# lymeshield_system.net
KiCad netlist of a schematic drawn in EAGLE
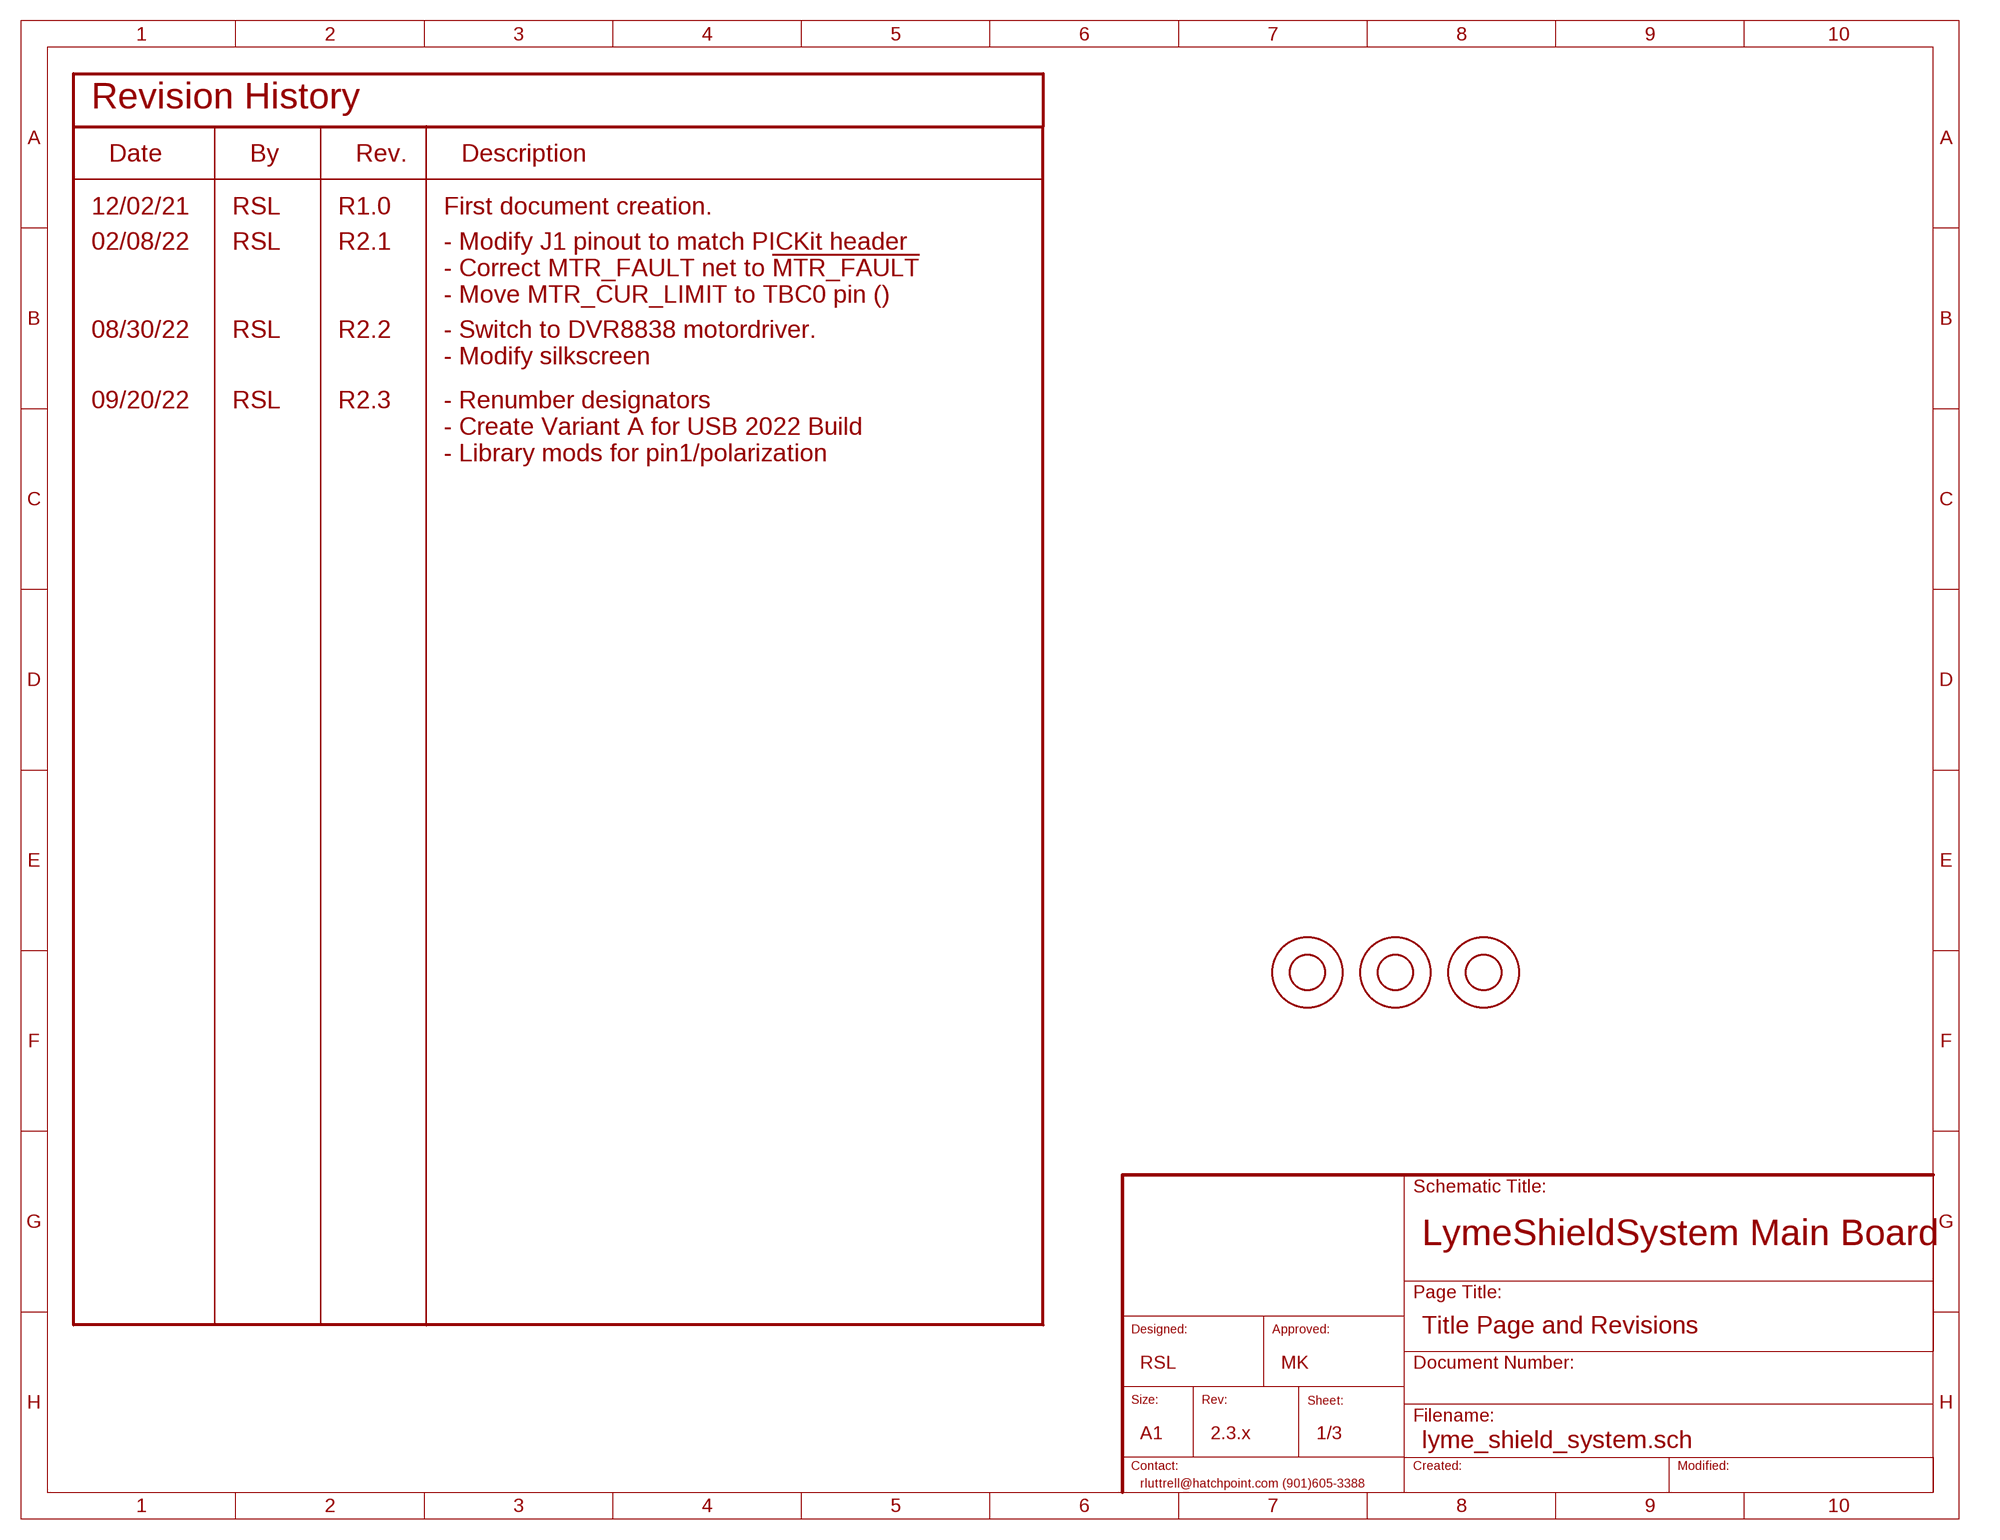
[diagram p0: schematic, sheet 1]
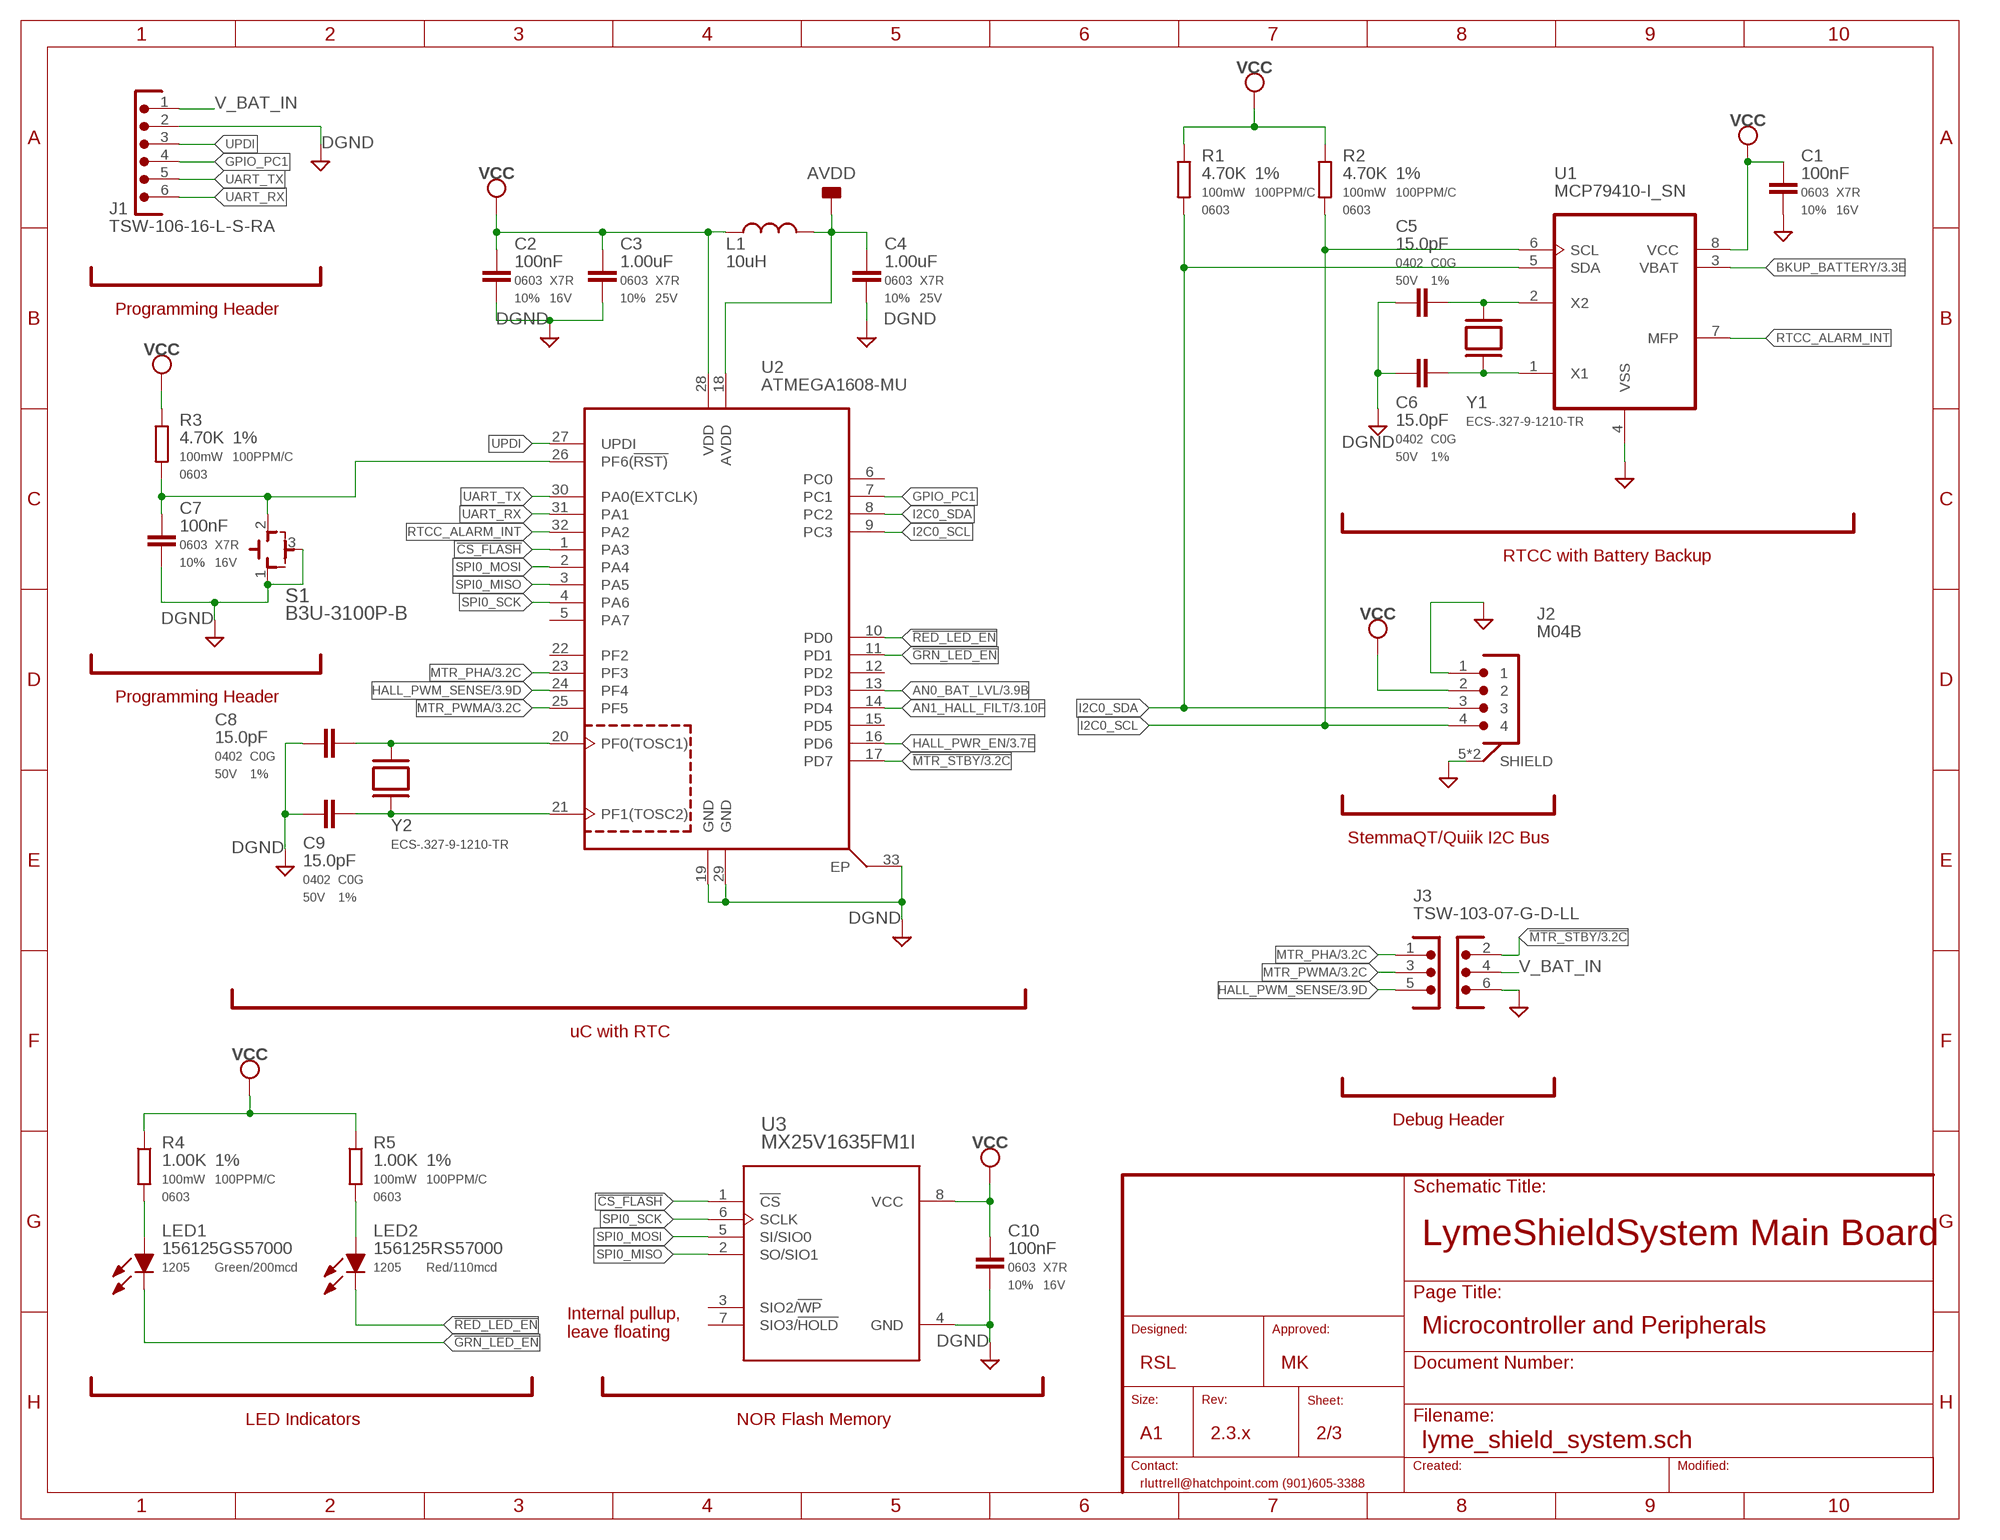
[diagram p1: schematic, sheet 2]
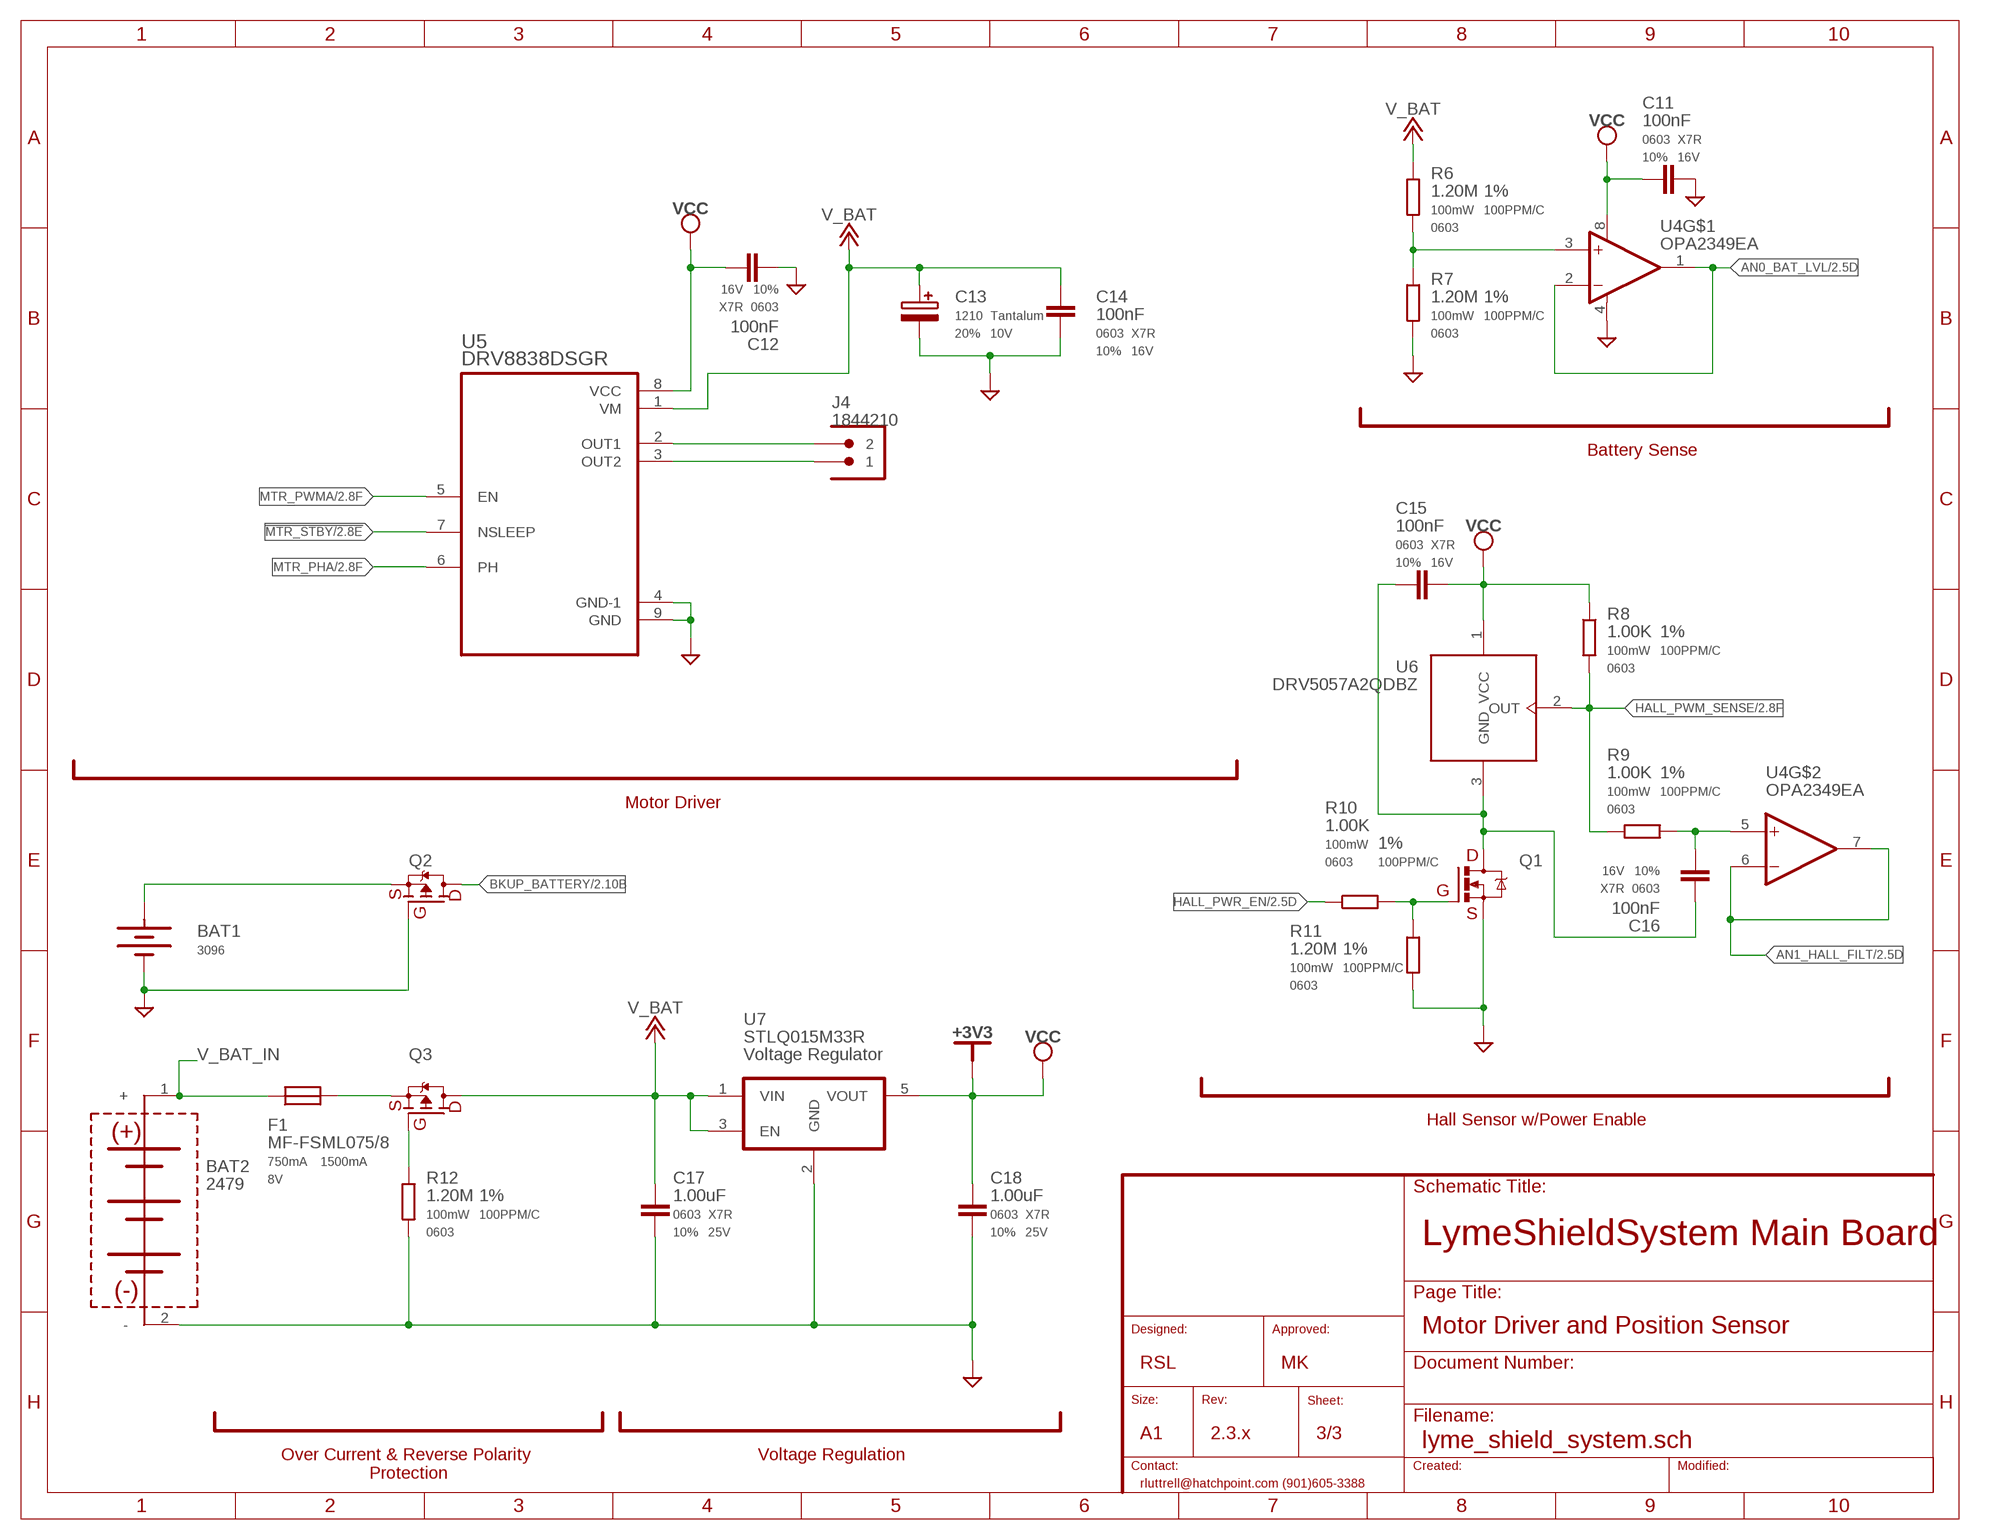
[diagram p2: schematic, sheet 3]

(export (version "E")
  (design (tool "Eeschema 10.0.6"))
  (components
    (comp (ref "FID1")
      (value "FIDUCIAL_1MM_TOP_BOTTOM")
      (footprint "eagle-import:FIDUCIAL_1MM_TOP_BOTTOM")
      (libsource (lib "eagle-import") (part "FIDUCIAL_1MM_TOP_BOTTOM"))
    )
    (comp (ref "FID2")
      (value "FIDUCIAL_1MM_TOP_BOTTOM")
      (footprint "eagle-import:FIDUCIAL_1MM_TOP_BOTTOM")
      (libsource (lib "eagle-import") (part "FIDUCIAL_1MM_TOP_BOTTOM"))
    )
    (comp (ref "FID3")
      (value "FIDUCIAL_1MM_TOP_BOTTOM")
      (footprint "eagle-import:FIDUCIAL_1MM_TOP_BOTTOM")
      (libsource (lib "eagle-import") (part "FIDUCIAL_1MM_TOP_BOTTOM"))
    )
    (comp (ref "BAT1")
      (value "3096")
      (footprint "eagle-import:3096")
      (fields (field (name "MOUSER_PART_NUMBER") "534-3096"))
      (libsource (lib "eagle-import") (part "3096"))
    )
    (comp (ref "BAT2")
      (value "2479")
      (footprint "eagle-import:2479")
      (fields (field (name "MOUSER_PART_NUMBER") "534-2479"))
      (libsource (lib "eagle-import") (part "2479"))
    )
    (comp (ref "C11")
      (value "100nF")
      (footprint "eagle-import:CAPC_0603_1608X90N")
      (fields
        (field (name "MANUFACTURER") "Murata")
        (field (name "PACKAGE") "0603")
        (field (name "TOL") "10%")
        (field (name "TYPE") "X7R")
        (field (name "VDC") "16V")
      )
      (libsource (lib "eagle-import") (part "GCM?188R71C104KA37J"))
    )
    (comp (ref "C12")
      (value "100nF")
      (footprint "eagle-import:CAPC_0603_1608X90N")
      (fields
        (field (name "MANUFACTURER") "Murata")
        (field (name "PACKAGE") "0603")
        (field (name "TOL") "10%")
        (field (name "TYPE") "X7R")
        (field (name "VDC") "16V")
      )
      (libsource (lib "eagle-import") (part "GCM?188R71C104KA37J"))
    )
    (comp (ref "C13")
      (value "TAJB226M010RNJ")
      (footprint "eagle-import:PCAPC_1210")
      (fields
        (field (name "MANUFACTURER") "AVX")
        (field (name "PACKAGE") "1210")
        (field (name "TOL") "20%")
        (field (name "TYPE") "Tantalum")
        (field (name "VDC") "10V")
        (field (name "TYPE_1") "Tantalum")
      )
      (libsource (lib "eagle-import") (part "TAJ?B226M010RNJ"))
    )
    (comp (ref "C14")
      (value "100nF")
      (footprint "eagle-import:CAPC_0603_1608X90N")
      (fields
        (field (name "MANUFACTURER") "Murata")
        (field (name "PACKAGE") "0603")
        (field (name "TOL") "10%")
        (field (name "TYPE") "X7R")
        (field (name "VDC") "16V")
      )
      (libsource (lib "eagle-import") (part "GCM?188R71C104KA37J"))
    )
    (comp (ref "C15")
      (value "100nF")
      (footprint "eagle-import:CAPC_0603_1608X90N")
      (fields
        (field (name "MANUFACTURER") "Murata")
        (field (name "PACKAGE") "0603")
        (field (name "TOL") "10%")
        (field (name "TYPE") "X7R")
        (field (name "VDC") "16V")
      )
      (libsource (lib "eagle-import") (part "GCM?188R71C104KA37J"))
    )
    (comp (ref "C16")
      (value "100nF")
      (footprint "eagle-import:CAPC_0603_1608X90N")
      (fields
        (field (name "MANUFACTURER") "Murata")
        (field (name "PACKAGE") "0603")
        (field (name "TOL") "10%")
        (field (name "TYPE") "X7R")
        (field (name "VDC") "16V")
      )
      (libsource (lib "eagle-import") (part "GCM?188R71C104KA37J"))
    )
    (comp (ref "C17")
      (value "1.00uF")
      (footprint "eagle-import:CAPC_0603_1608X90N")
      (fields
        (field (name "MANUFACTURER") "Murata")
        (field (name "PACKAGE") "0603")
        (field (name "TOL") "10%")
        (field (name "TYPE") "X7R")
        (field (name "VDC") "25V")
      )
      (libsource (lib "eagle-import") (part "GCM?188R71E105KA64D"))
    )
    (comp (ref "C18")
      (value "1.00uF")
      (footprint "eagle-import:CAPC_0603_1608X90N")
      (fields
        (field (name "MANUFACTURER") "Murata")
        (field (name "PACKAGE") "0603")
        (field (name "TOL") "10%")
        (field (name "TYPE") "X7R")
        (field (name "VDC") "25V")
      )
      (libsource (lib "eagle-import") (part "GCM?188R71E105KA64D"))
    )
    (comp (ref "F1")
      (value "MF-FSML075/8")
      (footprint "eagle-import:FUSC1608X70N")
      (fields (field (name "IHOLD") "750mA") (field (name "ITRIP") "1500mA") (field (name "VMAX") "8V"))
      (libsource (lib "eagle-import") (part "MF-FSML?075/8"))
    )
    (comp (ref "J4")
      (value "1844210")
      (footprint "eagle-import:1844210-2-3.50")
      (libsource (lib "eagle-import") (part "1844210"))
    )
    (comp (ref "Q1")
      (value "FDN5632N-F085-FDN5632N_F085")
      (footprint "eagle-import:SOT-23")
      (fields (field (name "MANUFACTURER") "ON Semiconductor"))
      (libsource (lib "eagle-import") (part "FDN5632N-F085-FDN5632N_F085"))
    )
    (comp (ref "Q2")
      (value "PMOS_DMP2035U-7")
      (footprint "eagle-import:SOT-23")
      (fields (field (name "MF") "Diodes Incorporated") (field (name "MP") "DMP2035U-7"))
      (libsource (lib "eagle-import") (part "PMOS_DMP2035U-7"))
    )
    (comp (ref "Q3")
      (value "PMOS_DMP2035U-7")
      (footprint "eagle-import:SOT-23")
      (fields (field (name "MF") "Diodes Incorporated") (field (name "MP") "DMP2035U-7"))
      (libsource (lib "eagle-import") (part "PMOS_DMP2035U-7"))
    )
    (comp (ref "R6")
      (value "1.20M")
      (footprint "eagle-import:R0603K")
      (fields
        (field (name "MF") "Vishay")
        (field (name "PACKAGE") "0603")
        (field (name "PWR_RATE") "100mW")
        (field (name "TEMPCO") "100PPM/C")
        (field (name "TOLERANCE") "1%")
      )
      (libsource (lib "eagle-import") (part "CRCW?06031M20FKEA"))
    )
    (comp (ref "R7")
      (value "1.20M")
      (footprint "eagle-import:R0603K")
      (fields
        (field (name "MF") "Vishay")
        (field (name "PACKAGE") "0603")
        (field (name "PWR_RATE") "100mW")
        (field (name "TEMPCO") "100PPM/C")
        (field (name "TOLERANCE") "1%")
      )
      (libsource (lib "eagle-import") (part "CRCW?06031M20FKEA"))
    )
    (comp (ref "R8")
      (value "1.00K")
      (footprint "eagle-import:R0603K")
      (fields
        (field (name "MF") "Vishay")
        (field (name "PACKAGE") "0603")
        (field (name "PWR_RATE") "100mW")
        (field (name "TEMPCO") "100PPM/C")
        (field (name "TOLERANCE") "1%")
      )
      (libsource (lib "eagle-import") (part "CRCW?06031K00FKEAC"))
    )
    (comp (ref "R9")
      (value "1.00K")
      (footprint "eagle-import:R0603K")
      (fields
        (field (name "MF") "Vishay")
        (field (name "PACKAGE") "0603")
        (field (name "PWR_RATE") "100mW")
        (field (name "TEMPCO") "100PPM/C")
        (field (name "TOLERANCE") "1%")
      )
      (libsource (lib "eagle-import") (part "CRCW?06031K00FKEAC"))
    )
    (comp (ref "R10")
      (value "1.00K")
      (footprint "eagle-import:R0603K")
      (fields
        (field (name "MF") "Vishay")
        (field (name "PACKAGE") "0603")
        (field (name "PWR_RATE") "100mW")
        (field (name "TEMPCO") "100PPM/C")
        (field (name "TOLERANCE") "1%")
      )
      (libsource (lib "eagle-import") (part "CRCW?06031K00FKEAC"))
    )
    (comp (ref "R11")
      (value "1.20M")
      (footprint "eagle-import:R0603K")
      (fields
        (field (name "MF") "Vishay")
        (field (name "PACKAGE") "0603")
        (field (name "PWR_RATE") "100mW")
        (field (name "TEMPCO") "100PPM/C")
        (field (name "TOLERANCE") "1%")
      )
      (libsource (lib "eagle-import") (part "CRCW?06031M20FKEA"))
    )
    (comp (ref "R12")
      (value "1.20M")
      (footprint "eagle-import:R0603K")
      (fields
        (field (name "MF") "Vishay")
        (field (name "PACKAGE") "0603")
        (field (name "PWR_RATE") "100mW")
        (field (name "TEMPCO") "100PPM/C")
        (field (name "TOLERANCE") "1%")
      )
      (libsource (lib "eagle-import") (part "CRCW?06031M20FKEA"))
    )
    (comp (ref "U4")
      (value "OPA2349EA")
      (footprint "eagle-import:SOT65P280X145-8N")
      (fields
        (field (name "ARROW_PART_NUMBER") "OPA2349EA/3K")
        (field (name "MOUSER_PART_NUMBER") "595-OPA2349EA/3K")
      )
      (libsource (lib "eagle-import") (part "OPA2349EA"))
    )
    (comp (ref "U5")
      (value "DRV8838DSGR")
      (footprint "eagle-import:SON50P200X200X80-9N")
      (fields (field (name "MF") "Texas Instruments") (field (name "MP") "DRV8838DSGT"))
      (libsource (lib "eagle-import") (part "DRV8838DSGR"))
    )
    (comp (ref "U6")
      (value "DRV5057A2QDBZ")
      (footprint "eagle-import:SOT95P237X112-3N")
      (libsource (lib "eagle-import") (part "DRV5057QDBZA2"))
    )
    (comp (ref "U7")
      (value "STLQ015M33R")
      (footprint "eagle-import:SOT23-5L")
      (fields
        (field (name "DESC") "Voltage Regulator")
        (field (name "MF") "STM")
        (field (name "VOLTAGE") "3.3V")
      )
      (libsource (lib "eagle-import") (part "STLQ015MR33"))
    )
    (comp (ref "C1")
      (value "100nF")
      (footprint "eagle-import:CAPC_0603_1608X90N")
      (fields
        (field (name "MANUFACTURER") "Murata")
        (field (name "PACKAGE") "0603")
        (field (name "TOL") "10%")
        (field (name "TYPE") "X7R")
        (field (name "VDC") "16V")
      )
      (libsource (lib "eagle-import") (part "GCM?188R71C104KA37J"))
    )
    (comp (ref "C2")
      (value "100nF")
      (footprint "eagle-import:CAPC_0603_1608X90N")
      (fields
        (field (name "MANUFACTURER") "Murata")
        (field (name "PACKAGE") "0603")
        (field (name "TOL") "10%")
        (field (name "TYPE") "X7R")
        (field (name "VDC") "16V")
      )
      (libsource (lib "eagle-import") (part "GCM?188R71C104KA37J"))
    )
    (comp (ref "C3")
      (value "1.00uF")
      (footprint "eagle-import:CAPC_0603_1608X90N")
      (fields
        (field (name "MANUFACTURER") "Murata")
        (field (name "PACKAGE") "0603")
        (field (name "TOL") "10%")
        (field (name "TYPE") "X7R")
        (field (name "VDC") "25V")
      )
      (libsource (lib "eagle-import") (part "GCM?188R71E105KA64D"))
    )
    (comp (ref "C4")
      (value "1.00uF")
      (footprint "eagle-import:CAPC_0603_1608X90N")
      (fields
        (field (name "MANUFACTURER") "Murata")
        (field (name "PACKAGE") "0603")
        (field (name "TOL") "10%")
        (field (name "TYPE") "X7R")
        (field (name "VDC") "25V")
      )
      (libsource (lib "eagle-import") (part "GCM?188R71E105KA64D"))
    )
    (comp (ref "C5")
      (value "15.0pF")
      (footprint "eagle-import:CAPC_0402_1005X55N")
      (fields
        (field (name "MANUFACTURER") "Murata")
        (field (name "PACKAGE") "0402")
        (field (name "TOL") "1%")
        (field (name "TYPE") "C0G")
        (field (name "VDC") "50V")
      )
      (libsource (lib "eagle-import") (part "GCM?1555C1H150FA16D"))
    )
    (comp (ref "C6")
      (value "15.0pF")
      (footprint "eagle-import:CAPC_0402_1005X55N")
      (fields
        (field (name "MANUFACTURER") "Murata")
        (field (name "PACKAGE") "0402")
        (field (name "TOL") "1%")
        (field (name "TYPE") "C0G")
        (field (name "VDC") "50V")
      )
      (libsource (lib "eagle-import") (part "GCM?1555C1H150FA16D"))
    )
    (comp (ref "C7")
      (value "100nF")
      (footprint "eagle-import:CAPC_0603_1608X90N")
      (fields
        (field (name "MANUFACTURER") "Murata")
        (field (name "PACKAGE") "0603")
        (field (name "TOL") "10%")
        (field (name "TYPE") "X7R")
        (field (name "VDC") "16V")
      )
      (libsource (lib "eagle-import") (part "GCM?188R71C104KA37J"))
    )
    (comp (ref "C8")
      (value "15.0pF")
      (footprint "eagle-import:CAPC_0402_1005X55N")
      (fields
        (field (name "MANUFACTURER") "Murata")
        (field (name "PACKAGE") "0402")
        (field (name "TOL") "1%")
        (field (name "TYPE") "C0G")
        (field (name "VDC") "50V")
      )
      (libsource (lib "eagle-import") (part "GCM?1555C1H150FA16D"))
    )
    (comp (ref "C9")
      (value "15.0pF")
      (footprint "eagle-import:CAPC_0402_1005X55N")
      (fields
        (field (name "MANUFACTURER") "Murata")
        (field (name "PACKAGE") "0402")
        (field (name "TOL") "1%")
        (field (name "TYPE") "C0G")
        (field (name "VDC") "50V")
      )
      (libsource (lib "eagle-import") (part "GCM?1555C1H150FA16D"))
    )
    (comp (ref "C10")
      (value "100nF")
      (footprint "eagle-import:CAPC_0603_1608X90N")
      (fields
        (field (name "MANUFACTURER") "Murata")
        (field (name "PACKAGE") "0603")
        (field (name "TOL") "10%")
        (field (name "TYPE") "X7R")
        (field (name "VDC") "16V")
      )
      (libsource (lib "eagle-import") (part "GCM?188R71C104KA37J"))
    )
    (comp (ref "J1")
      (value "TSW-106-16-L-S-RA")
      (footprint "eagle-import:HDR-100MIL-1X6-THRU-RA")
      (libsource (lib "eagle-import") (part "TSW-106-16-L-S-RA"))
    )
    (comp (ref "J2")
      (value "M04B")
      (footprint "eagle-import:SM04B-SRSS-TB(LFSN)")
      (fields (field (name "MANUFACTURER_PART_NUMBER") "SM04B-SRSS-TB(LFSN)"))
      (libsource (lib "eagle-import") (part "?M04B"))
    )
    (comp (ref "J3")
      (value "TSW-103-07-G-D-LL")
      (footprint "eagle-import:HDRV6W64P254_2X3_762X495X838P")
      (fields (field (name "MOUSER_PART_NUMBER") "200-TSW10307GDLL"))
      (libsource (lib "eagle-import") (part "TSW-103-07-G-D-LL"))
    )
    (comp (ref "L1")
      (value "10uH")
      (footprint "eagle-import:INDC1608X90N")
      (fields (field (name "MF") "Taiyo Yuden") (field (name "MP") "LB1608T100M"))
      (libsource (lib "eagle-import") (part "LB1608T100M"))
    )
    (comp (ref "LED1")
      (value "156125GS57000")
      (footprint "eagle-import:LEDC3212X120N")
      (fields (field (name "PACKAGE") "1205"))
      (libsource (lib "eagle-import") (part "15612557000GS"))
    )
    (comp (ref "LED2")
      (value "156125RS57000")
      (footprint "eagle-import:LEDC3212X120N")
      (fields (field (name "PACKAGE") "1205"))
      (libsource (lib "eagle-import") (part "15612557000RS"))
    )
    (comp (ref "R1")
      (value "4.70K")
      (footprint "eagle-import:R0603K")
      (fields
        (field (name "MF") "Vishay")
        (field (name "PACKAGE") "0603")
        (field (name "PWR_RATE") "100mW")
        (field (name "TEMPCO") "100PPM/C")
        (field (name "TOLERANCE") "1%")
      )
      (libsource (lib "eagle-import") (part "CRCW?06034K70FKEA"))
    )
    (comp (ref "R2")
      (value "4.70K")
      (footprint "eagle-import:R0603K")
      (fields
        (field (name "MF") "Vishay")
        (field (name "PACKAGE") "0603")
        (field (name "PWR_RATE") "100mW")
        (field (name "TEMPCO") "100PPM/C")
        (field (name "TOLERANCE") "1%")
      )
      (libsource (lib "eagle-import") (part "CRCW?06034K70FKEA"))
    )
    (comp (ref "R3")
      (value "4.70K")
      (footprint "eagle-import:R0603K")
      (fields
        (field (name "MF") "Vishay")
        (field (name "PACKAGE") "0603")
        (field (name "PWR_RATE") "100mW")
        (field (name "TEMPCO") "100PPM/C")
        (field (name "TOLERANCE") "1%")
      )
      (libsource (lib "eagle-import") (part "CRCW?06034K70FKEA"))
    )
    (comp (ref "R4")
      (value "1.00K")
      (footprint "eagle-import:R0603K")
      (fields
        (field (name "MF") "Vishay")
        (field (name "PACKAGE") "0603")
        (field (name "PWR_RATE") "100mW")
        (field (name "TEMPCO") "100PPM/C")
        (field (name "TOLERANCE") "1%")
      )
      (libsource (lib "eagle-import") (part "CRCW?06031K00FKEAC"))
    )
    (comp (ref "R5")
      (value "1.00K")
      (footprint "eagle-import:R0603K")
      (fields
        (field (name "MF") "Vishay")
        (field (name "PACKAGE") "0603")
        (field (name "PWR_RATE") "100mW")
        (field (name "TEMPCO") "100PPM/C")
        (field (name "TOLERANCE") "1%")
      )
      (libsource (lib "eagle-import") (part "CRCW?06031K00FKEAC"))
    )
    (comp (ref "S1")
      (value "B3U-3100P-B")
      (footprint "eagle-import:B3U-3100P-B")
      (libsource (lib "eagle-import") (part "B3U-3100P-B"))
    )
    (comp (ref "U1")
      (value "MCP79410-I_SN")
      (footprint "eagle-import:SOIC127P600X175-8N")
      (fields
        (field (name "ARROW_PART_NUMBER") "MCP79410-I/SN")
        (field (name "MOUSER_PART_NUMBER") "579-MCP79410-I/SN")
      )
      (libsource (lib "eagle-import") (part "MCP79410-I_SN"))
    )
    (comp (ref "U2")
      (value "ATMEGA1608-MU")
      (footprint "eagle-import:QFN50P500X500X90-33N")
      (fields (field (name "MOUSER_PART_NUMBER") "556-ATMEGA1608-MU"))
      (libsource (lib "eagle-import") (part "ATMEGA1608-MU"))
    )
    (comp (ref "U3")
      (value "MX25V1635FM1I")
      (footprint "eagle-import:SOIC127P600X175-8N")
      (fields (field (name "MANUFACTURER") "Macronix"))
      (libsource (lib "eagle-import") (part "MX25V?M1I1635F"))
    )
    (comp (ref "Y1")
      (value "ECS-.327-9-1210-TR")
      (footprint "eagle-import:XTAL_ECS-.327-9-1210-TR")
      (fields (field (name "DIGI-KEY_PART_NUMBER") "XC2283CT-ND") (field (name "MF") "ECS Inc."))
      (libsource (lib "eagle-import") (part "ECS-.327-9-1210-TR"))
    )
    (comp (ref "Y2")
      (value "ECS-.327-9-1210-TR")
      (footprint "eagle-import:XTAL_ECS-.327-9-1210-TR")
      (fields (field (name "DIGI-KEY_PART_NUMBER") "XC2283CT-ND") (field (name "MF") "ECS Inc."))
      (libsource (lib "eagle-import") (part "ECS-.327-9-1210-TR"))
    )
  )
  (nets
    (net (code "1") (name "+3V3") (class "Default")
      (node (ref "C1") (pin "1") (pinfunction "1_1") (pintype "passive"))
      (node (ref "C10") (pin "1") (pinfunction "1_1") (pintype "passive"))
      (node (ref "C11") (pin "2") (pinfunction "2_2") (pintype "passive"))
      (node (ref "C12") (pin "1") (pinfunction "1_1") (pintype "passive"))
      (node (ref "C15") (pin "1") (pinfunction "1_1") (pintype "passive"))
      (node (ref "C18") (pin "1") (pinfunction "1_1") (pintype "passive"))
      (node (ref "C2") (pin "1") (pinfunction "1_1") (pintype "passive"))
      (node (ref "C3") (pin "1") (pinfunction "1_1") (pintype "passive"))
      (node (ref "J2") (pin "2") (pinfunction "2_2") (pintype "bidirectional"))
      (node (ref "L1") (pin "1") (pinfunction "1_1") (pintype "passive"))
      (node (ref "R1") (pin "1") (pinfunction "1_1") (pintype "passive"))
      (node (ref "R2") (pin "1") (pinfunction "1_1") (pintype "passive"))
      (node (ref "R3") (pin "1") (pinfunction "1_1") (pintype "passive"))
      (node (ref "R4") (pin "1") (pinfunction "1_1") (pintype "passive"))
      (node (ref "R5") (pin "1") (pinfunction "1_1") (pintype "passive"))
      (node (ref "R8") (pin "1") (pinfunction "1_1") (pintype "passive"))
      (node (ref "U1") (pin "8") (pinfunction "VCC_8") (pintype "bidirectional"))
      (node (ref "U2") (pin "28") (pinfunction "VDD_28") (pintype "bidirectional"))
      (node (ref "U3") (pin "8") (pinfunction "VCC_8") (pintype "power_in"))
      (node (ref "U4") (pin "8") (pinfunction "V+_8") (pintype "power_in"))
      (node (ref "U5") (pin "8") (pinfunction "VCC_8") (pintype "power_in"))
      (node (ref "U6") (pin "1") (pinfunction "VCC_1") (pintype "bidirectional"))
      (node (ref "U7") (pin "5") (pinfunction "VOUT_5") (pintype "power_in"))
    )
    (net (code "2") (name "AN0_BAT_LVL") (class "Default")
      (node (ref "U2") (pin "13") (pinfunction "PD3_13") (pintype "bidirectional"))
      (node (ref "U4") (pin "1") (pinfunction "OUT_1") (pintype "output"))
      (node (ref "U4") (pin "2") (pinfunction "-IN_2") (pintype "input"))
    )
    (net (code "3") (name "AN1_HALL_FILT") (class "Default")
      (node (ref "U2") (pin "14") (pinfunction "PD4_14") (pintype "bidirectional"))
      (node (ref "U4") (pin "6") (pinfunction "-IN_6") (pintype "input"))
      (node (ref "U4") (pin "7") (pinfunction "OUT_7") (pintype "output"))
    )
    (net (code "4") (name "AVDD") (class "Default")
      (node (ref "C4") (pin "1") (pinfunction "1_1") (pintype "passive"))
      (node (ref "L1") (pin "2") (pinfunction "2_2") (pintype "passive"))
      (node (ref "U2") (pin "18") (pinfunction "AVDD_18") (pintype "bidirectional"))
    )
    (net (code "5") (name "BKUP_BATTERY") (class "Default")
      (node (ref "Q2") (pin "1") (pinfunction "D_1") (pintype "passive"))
      (node (ref "U1") (pin "3") (pinfunction "VBAT_3") (pintype "bidirectional"))
    )
    (net (code "6") (name "DGND") (class "Default")
      (node (ref "BAT1") (pin "1") (pinfunction "-_1") (pintype "power_in"))
      (node (ref "BAT1") (pin "3") (pinfunction "-_3") (pintype "power_in"))
      (node (ref "BAT2") (pin "2") (pinfunction "-_2") (pintype "bidirectional"))
      (node (ref "C1") (pin "2") (pinfunction "2_2") (pintype "passive"))
      (node (ref "C10") (pin "2") (pinfunction "2_2") (pintype "passive"))
      (node (ref "C11") (pin "1") (pinfunction "1_1") (pintype "passive"))
      (node (ref "C12") (pin "2") (pinfunction "2_2") (pintype "passive"))
      (node (ref "C13") (pin "2") (pinfunction "-_2") (pintype "bidirectional"))
      (node (ref "C14") (pin "2") (pinfunction "2_2") (pintype "passive"))
      (node (ref "C17") (pin "2") (pinfunction "2_2") (pintype "passive"))
      (node (ref "C18") (pin "2") (pinfunction "2_2") (pintype "passive"))
      (node (ref "C2") (pin "2") (pinfunction "2_2") (pintype "passive"))
      (node (ref "C3") (pin "2") (pinfunction "2_2") (pintype "passive"))
      (node (ref "C4") (pin "2") (pinfunction "2_2") (pintype "passive"))
      (node (ref "C5") (pin "2") (pinfunction "2_2") (pintype "passive"))
      (node (ref "C6") (pin "2") (pinfunction "2_2") (pintype "passive"))
      (node (ref "C7") (pin "2") (pinfunction "2_2") (pintype "passive"))
      (node (ref "C8") (pin "2") (pinfunction "2_2") (pintype "passive"))
      (node (ref "C9") (pin "2") (pinfunction "2_2") (pintype "passive"))
      (node (ref "J1") (pin "2") (pinfunction "2_2") (pintype "passive"))
      (node (ref "J2") (pin "1") (pinfunction "1_1") (pintype "bidirectional"))
      (node (ref "J2") (pin "5") (pinfunction "SHIELD_5") (pintype "bidirectional"))
      (node (ref "J2") (pin "6") (pinfunction "SHIELD_6") (pintype "bidirectional"))
      (node (ref "J3") (pin "6") (pinfunction "6_6") (pintype "passive"))
      (node (ref "Q1") (pin "2") (pinfunction "S_2") (pintype "passive"))
      (node (ref "Q2") (pin "3") (pinfunction "G_3") (pintype "passive"))
      (node (ref "R11") (pin "2") (pinfunction "2_2") (pintype "passive"))
      (node (ref "R12") (pin "2") (pinfunction "2_2") (pintype "passive"))
      (node (ref "R7") (pin "2") (pinfunction "2_2") (pintype "passive"))
      (node (ref "S1") (pin "1") (pinfunction "COM_1") (pintype "bidirectional"))
      (node (ref "S1") (pin "3") (pinfunction "COM1_3") (pintype "bidirectional"))
      (node (ref "U1") (pin "4") (pinfunction "VSS_4") (pintype "bidirectional"))
      (node (ref "U2") (pin "19") (pinfunction "GND_19") (pintype "bidirectional"))
      (node (ref "U2") (pin "29") (pinfunction "GND_29") (pintype "bidirectional"))
      (node (ref "U2") (pin "33") (pinfunction "EP_33") (pintype "bidirectional"))
      (node (ref "U3") (pin "4") (pinfunction "GND_4") (pintype "passive"))
      (node (ref "U4") (pin "4") (pinfunction "V-_4") (pintype "power_in"))
      (node (ref "U5") (pin "4") (pinfunction "GND-1_4") (pintype "power_in"))
      (node (ref "U5") (pin "9") (pinfunction "GND_9") (pintype "power_in"))
      (node (ref "U7") (pin "2") (pinfunction "GND_2") (pintype "power_in"))
    )
    (net (code "7") (name "GPIO_PC1") (class "Default")
      (node (ref "J1") (pin "4") (pinfunction "4_4") (pintype "passive"))
      (node (ref "U2") (pin "7") (pinfunction "PC1_7") (pintype "bidirectional"))
    )
    (net (code "8") (name "HALL_PWM_SENSE") (class "Default")
      (node (ref "J3") (pin "5") (pinfunction "5_5") (pintype "passive"))
      (node (ref "R8") (pin "2") (pinfunction "2_2") (pintype "passive"))
      (node (ref "R9") (pin "1") (pinfunction "1_1") (pintype "passive"))
      (node (ref "U2") (pin "24") (pinfunction "PF4_24") (pintype "bidirectional"))
      (node (ref "U6") (pin "2") (pinfunction "OUT_2") (pintype "bidirectional"))
    )
    (net (code "9") (name "HALL_PWR_EN") (class "Default")
      (node (ref "R10") (pin "1") (pinfunction "1_1") (pintype "passive"))
      (node (ref "U2") (pin "16") (pinfunction "PD6_16") (pintype "bidirectional"))
    )
    (net (code "10") (name "I2C0_SCL") (class "Default")
      (node (ref "J2") (pin "4") (pinfunction "4_4") (pintype "bidirectional"))
      (node (ref "R2") (pin "2") (pinfunction "2_2") (pintype "passive"))
      (node (ref "U1") (pin "6") (pinfunction "SCL_6") (pintype "input"))
      (node (ref "U2") (pin "9") (pinfunction "PC3_9") (pintype "bidirectional"))
    )
    (net (code "11") (name "I2C0_SDA") (class "Default")
      (node (ref "J2") (pin "3") (pinfunction "3_3") (pintype "bidirectional"))
      (node (ref "R1") (pin "2") (pinfunction "2_2") (pintype "passive"))
      (node (ref "U1") (pin "5") (pinfunction "SDA_5") (pintype "bidirectional"))
      (node (ref "U2") (pin "8") (pinfunction "PC2_8") (pintype "bidirectional"))
    )
    (net (code "12") (name "MTR_PHA") (class "Default")
      (node (ref "J3") (pin "1") (pinfunction "1_1") (pintype "passive"))
      (node (ref "U2") (pin "23") (pinfunction "PF3_23") (pintype "bidirectional"))
      (node (ref "U5") (pin "6") (pinfunction "PH_6") (pintype "bidirectional"))
    )
    (net (code "13") (name "MTR_PWMA") (class "Default")
      (node (ref "J3") (pin "3") (pinfunction "3_3") (pintype "passive"))
      (node (ref "U2") (pin "25") (pinfunction "PF5_25") (pintype "bidirectional"))
      (node (ref "U5") (pin "5") (pinfunction "EN_5") (pintype "bidirectional"))
    )
    (net (code "14") (name "Net-(BAT1-+)") (class "Default")
      (node (ref "BAT1") (pin "2") (pinfunction "+_2") (pintype "power_in"))
      (node (ref "Q2") (pin "2") (pinfunction "S_2") (pintype "passive"))
    )
    (net (code "15") (name "Net-(J4-1)") (class "Default")
      (node (ref "J4") (pin "P$1") (pinfunction "1_P$1") (pintype "bidirectional"))
      (node (ref "U5") (pin "3") (pinfunction "OUT2_3") (pintype "output"))
    )
    (net (code "16") (name "Net-(J4-2)") (class "Default")
      (node (ref "J4") (pin "P$2") (pinfunction "2_P$2") (pintype "bidirectional"))
      (node (ref "U5") (pin "2") (pinfunction "OUT1_2") (pintype "output"))
    )
    (net (code "17") (name "Net-(LED1-A)") (class "Default")
      (node (ref "LED1") (pin "2") (pinfunction "A_2") (pintype "bidirectional"))
      (node (ref "R4") (pin "2") (pinfunction "2_2") (pintype "passive"))
    )
    (net (code "18") (name "Net-(LED2-A)") (class "Default")
      (node (ref "LED2") (pin "2") (pinfunction "A_2") (pintype "bidirectional"))
      (node (ref "R5") (pin "2") (pinfunction "2_2") (pintype "passive"))
    )
    (net (code "19") (name "Net-(Q1-D)") (class "Default")
      (node (ref "C15") (pin "2") (pinfunction "2_2") (pintype "passive"))
      (node (ref "C16") (pin "2") (pinfunction "2_2") (pintype "passive"))
      (node (ref "Q1") (pin "1") (pinfunction "D_1") (pintype "passive"))
      (node (ref "U6") (pin "3") (pinfunction "GND_3") (pintype "bidirectional"))
    )
    (net (code "20") (name "Net-(Q1-G)") (class "Default")
      (node (ref "Q1") (pin "3") (pinfunction "G_3") (pintype "passive"))
      (node (ref "R10") (pin "2") (pinfunction "2_2") (pintype "passive"))
      (node (ref "R11") (pin "1") (pinfunction "1_1") (pintype "passive"))
    )
    (net (code "21") (name "Net-(Q3-G)") (class "Default")
      (node (ref "Q3") (pin "3") (pinfunction "G_3") (pintype "passive"))
      (node (ref "R12") (pin "1") (pinfunction "1_1") (pintype "passive"))
    )
    (net (code "22") (name "Net-(Q3-S)") (class "Default")
      (node (ref "F1") (pin "2") (pinfunction "2_2") (pintype "bidirectional"))
      (node (ref "Q3") (pin "2") (pinfunction "S_2") (pintype "passive"))
    )
    (net (code "23") (name "Net-(S1-NO)") (class "Default")
      (node (ref "C7") (pin "1") (pinfunction "1_1") (pintype "passive"))
      (node (ref "R3") (pin "2") (pinfunction "2_2") (pintype "passive"))
      (node (ref "S1") (pin "2") (pinfunction "NO_2") (pintype "bidirectional"))
      (node (ref "U2") (pin "26") (pinfunction "PF6(~{RST})_26") (pintype "bidirectional"))
    )
    (net (code "24") (name "Net-(U1-X1)") (class "Default")
      (node (ref "C6") (pin "1") (pinfunction "1_1") (pintype "passive"))
      (node (ref "U1") (pin "1") (pinfunction "X1_1") (pintype "input"))
      (node (ref "Y1") (pin "2") (pinfunction "2_2") (pintype "passive"))
    )
    (net (code "25") (name "Net-(U1-X2)") (class "Default")
      (node (ref "C5") (pin "1") (pinfunction "1_1") (pintype "passive"))
      (node (ref "U1") (pin "2") (pinfunction "X2_2") (pintype "input"))
      (node (ref "Y1") (pin "1") (pinfunction "1_1") (pintype "passive"))
    )
    (net (code "26") (name "Net-(U2-PF0(TOSC1))") (class "Default")
      (node (ref "C8") (pin "1") (pinfunction "1_1") (pintype "passive"))
      (node (ref "U2") (pin "20") (pinfunction "PF0(TOSC1)_20") (pintype "bidirectional"))
      (node (ref "Y2") (pin "1") (pinfunction "1_1") (pintype "passive"))
    )
    (net (code "27") (name "Net-(U2-PF1(TOSC2))") (class "Default")
      (node (ref "C9") (pin "1") (pinfunction "1_1") (pintype "passive"))
      (node (ref "U2") (pin "21") (pinfunction "PF1(TOSC2)_21") (pintype "bidirectional"))
      (node (ref "Y2") (pin "2") (pinfunction "2_2") (pintype "passive"))
    )
    (net (code "28") (name "Net-(U4A-+IN)") (class "Default")
      (node (ref "R6") (pin "2") (pinfunction "2_2") (pintype "passive"))
      (node (ref "R7") (pin "1") (pinfunction "1_1") (pintype "passive"))
      (node (ref "U4") (pin "3") (pinfunction "+IN_3") (pintype "input"))
    )
    (net (code "29") (name "Net-(U4B-+IN)") (class "Default")
      (node (ref "C16") (pin "1") (pinfunction "1_1") (pintype "passive"))
      (node (ref "R9") (pin "2") (pinfunction "2_2") (pintype "passive"))
      (node (ref "U4") (pin "5") (pinfunction "+IN_5") (pintype "input"))
    )
    (net (code "30") (name "RTCC_ALARM_INT") (class "Default")
      (node (ref "U1") (pin "7") (pinfunction "MFP_7") (pintype "bidirectional"))
      (node (ref "U2") (pin "32") (pinfunction "PA2_32") (pintype "bidirectional"))
    )
    (net (code "31") (name "SPI0_MISO") (class "Default")
      (node (ref "U2") (pin "3") (pinfunction "PA5_3") (pintype "bidirectional"))
      (node (ref "U3") (pin "2") (pinfunction "SO/SIO1_2") (pintype "bidirectional"))
    )
    (net (code "32") (name "SPI0_MOSI") (class "Default")
      (node (ref "U2") (pin "2") (pinfunction "PA4_2") (pintype "bidirectional"))
      (node (ref "U3") (pin "5") (pinfunction "SI/SIO0_5") (pintype "bidirectional"))
    )
    (net (code "33") (name "SPI0_SCK") (class "Default")
      (node (ref "U2") (pin "4") (pinfunction "PA6_4") (pintype "bidirectional"))
      (node (ref "U3") (pin "6") (pinfunction "SCLK_6") (pintype "input"))
    )
    (net (code "34") (name "UART_RX") (class "Default")
      (node (ref "J1") (pin "6") (pinfunction "6_6") (pintype "passive"))
      (node (ref "U2") (pin "31") (pinfunction "PA1_31") (pintype "bidirectional"))
    )
    (net (code "35") (name "UART_TX") (class "Default")
      (node (ref "J1") (pin "5") (pinfunction "5_5") (pintype "passive"))
      (node (ref "U2") (pin "30") (pinfunction "PA0(EXTCLK)_30") (pintype "bidirectional"))
    )
    (net (code "36") (name "UPDI") (class "Default")
      (node (ref "J1") (pin "3") (pinfunction "3_3") (pintype "passive"))
      (node (ref "U2") (pin "27") (pinfunction "UPDI_27") (pintype "bidirectional"))
    )
    (net (code "37") (name "V_BAT") (class "Default")
      (node (ref "C13") (pin "1") (pinfunction "+_1") (pintype "bidirectional"))
      (node (ref "C14") (pin "1") (pinfunction "1_1") (pintype "passive"))
      (node (ref "C17") (pin "1") (pinfunction "1_1") (pintype "passive"))
      (node (ref "Q3") (pin "1") (pinfunction "D_1") (pintype "passive"))
      (node (ref "R6") (pin "1") (pinfunction "1_1") (pintype "passive"))
      (node (ref "U5") (pin "1") (pinfunction "VM_1") (pintype "power_in"))
      (node (ref "U7") (pin "1") (pinfunction "VIN_1") (pintype "power_in"))
      (node (ref "U7") (pin "3") (pinfunction "EN_3") (pintype "input"))
    )
    (net (code "38") (name "V_BAT_IN") (class "Default")
      (node (ref "BAT2") (pin "1") (pinfunction "+_1") (pintype "bidirectional"))
      (node (ref "F1") (pin "1") (pinfunction "1_1") (pintype "bidirectional"))
      (node (ref "J1") (pin "1") (pinfunction "1_1") (pintype "passive"))
      (node (ref "J3") (pin "4") (pinfunction "4_4") (pintype "passive"))
    )
    (net (code "39") (name "unconnected-(U2-PA7-Pad5)") (class "Default")
      (node (ref "U2") (pin "5") (pinfunction "PA7_5") (pintype "bidirectional"))
    )
    (net (code "40") (name "unconnected-(U2-PC0-Pad6)") (class "Default")
      (node (ref "U2") (pin "6") (pinfunction "PC0_6") (pintype "bidirectional"))
    )
    (net (code "41") (name "unconnected-(U2-PD2-Pad12)") (class "Default")
      (node (ref "U2") (pin "12") (pinfunction "PD2_12") (pintype "bidirectional"))
    )
    (net (code "42") (name "unconnected-(U2-PD5-Pad15)") (class "Default")
      (node (ref "U2") (pin "15") (pinfunction "PD5_15") (pintype "bidirectional"))
    )
    (net (code "43") (name "unconnected-(U2-PF2-Pad22)") (class "Default")
      (node (ref "U2") (pin "22") (pinfunction "PF2_22") (pintype "bidirectional"))
    )
    (net (code "44") (name "unconnected-(U3-SIO2{slash}~{WP}-Pad3)") (class "Default")
      (node (ref "U3") (pin "3") (pinfunction "SIO2/~{WP}_3") (pintype "bidirectional"))
    )
    (net (code "45") (name "unconnected-(U3-SIO3{slash}~{HOLD}-Pad7)") (class "Default")
      (node (ref "U3") (pin "7") (pinfunction "SIO3/~{HOLD}_7") (pintype "bidirectional"))
    )
    (net (code "46") (name "~{CS_FLASH}") (class "Default")
      (node (ref "U2") (pin "1") (pinfunction "PA3_1") (pintype "bidirectional"))
      (node (ref "U3") (pin "1") (pinfunction "~{CS}_1") (pintype "input"))
    )
    (net (code "47") (name "~{GRN_LED_EN}") (class "Default")
      (node (ref "LED1") (pin "1") (pinfunction "K_1") (pintype "bidirectional"))
      (node (ref "U2") (pin "11") (pinfunction "PD1_11") (pintype "bidirectional"))
    )
    (net (code "48") (name "~{MTR_STBY}") (class "Default")
      (node (ref "J3") (pin "2") (pinfunction "2_2") (pintype "passive"))
      (node (ref "U2") (pin "17") (pinfunction "PD7_17") (pintype "bidirectional"))
      (node (ref "U5") (pin "7") (pinfunction "NSLEEP_7") (pintype "bidirectional"))
    )
    (net (code "49") (name "~{RED_LED_EN}") (class "Default")
      (node (ref "LED2") (pin "1") (pinfunction "K_1") (pintype "bidirectional"))
      (node (ref "U2") (pin "10") (pinfunction "PD0_10") (pintype "bidirectional"))
    )
  )
)
